# PCB_CoLAB_Schematic.net
KiCad netlist of a schematic drawn in EAGLE
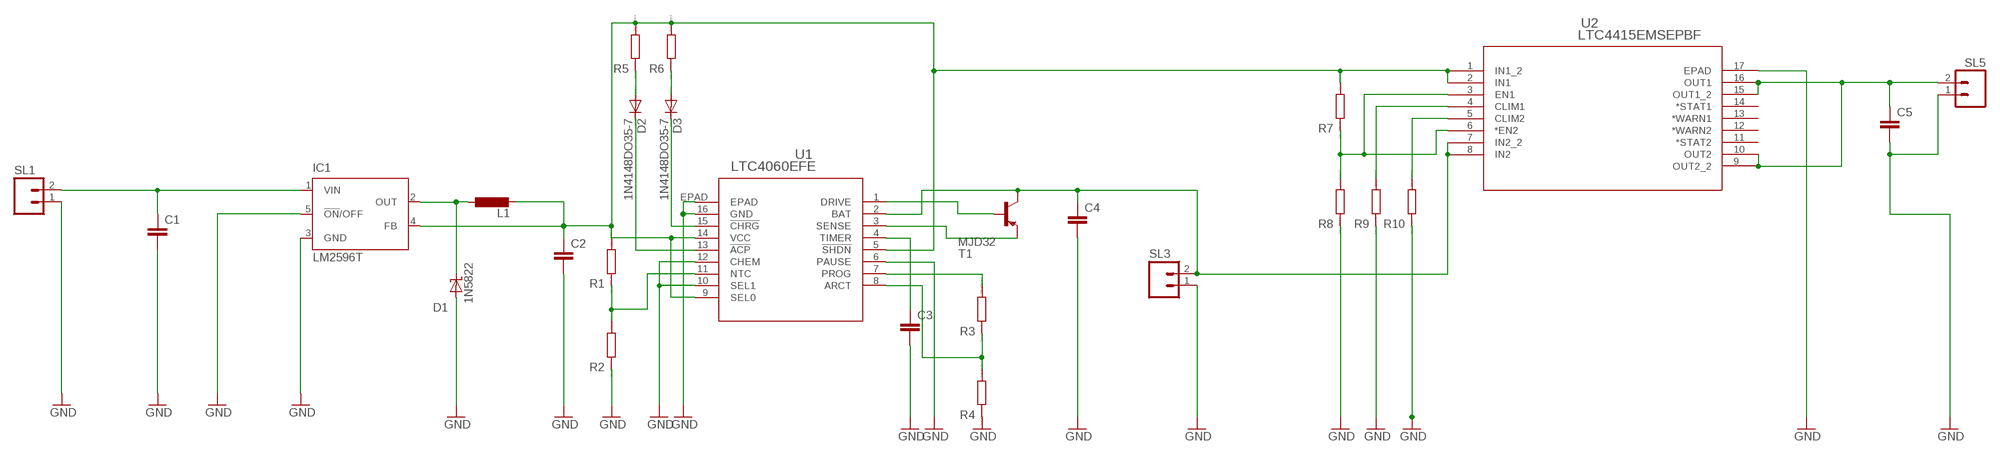
[diagram p0: schematic, sheet 1]

(export (version "E")
  (design (tool "Eeschema 10.0.6"))
  (components
    (comp (ref "C1")
      (value "C-EU025-024X044")
      (footprint "eagle-import:C025-024X044")
      (libsource (lib "eagle-import") (part "C-EU025-024X044"))
    )
    (comp (ref "C2")
      (value "C-EU025-024X044")
      (footprint "eagle-import:C025-024X044")
      (libsource (lib "eagle-import") (part "C-EU025-024X044"))
    )
    (comp (ref "C3")
      (value "C-EU025-024X044")
      (footprint "eagle-import:C025-024X044")
      (libsource (lib "eagle-import") (part "C-EU025-024X044"))
    )
    (comp (ref "C4")
      (value "C-EU025-024X044")
      (footprint "eagle-import:C025-024X044")
      (libsource (lib "eagle-import") (part "C-EU025-024X044"))
    )
    (comp (ref "C5")
      (value "C-EU025-024X044")
      (footprint "eagle-import:C025-024X044")
      (libsource (lib "eagle-import") (part "C-EU025-024X044"))
    )
    (comp (ref "D1")
      (value "1N5822")
      (footprint "eagle-import:DIOAD2120W130L950D530P")
      (fields (field (name "MF") "ON Semiconductor"))
      (libsource (lib "eagle-import") (part "1N5822"))
    )
    (comp (ref "D2")
      (value "1N4148DO35-7")
      (footprint "eagle-import:DO35-7")
      (libsource (lib "eagle-import") (part "1N4148DO35-7"))
    )
    (comp (ref "D3")
      (value "1N4148DO35-7")
      (footprint "eagle-import:DO35-7")
      (libsource (lib "eagle-import") (part "1N4148DO35-7"))
    )
    (comp (ref "IC1")
      (value "LM2596T")
      (footprint "eagle-import:T05D")
      (fields (field (name "MPN") "LM2596T-ADJ/LF02"))
      (libsource (lib "eagle-import") (part "LM2596T"))
    )
    (comp (ref "L1")
      (value "L-EU0204/7")
      (footprint "eagle-import:0204_7")
      (libsource (lib "eagle-import") (part "L-EU0204/7"))
    )
    (comp (ref "R1")
      (value "R0204/7")
      (footprint "eagle-import:0204_7")
      (libsource (lib "eagle-import") (part "R0204/7"))
    )
    (comp (ref "R2")
      (value "R0204/7")
      (footprint "eagle-import:0204_7")
      (libsource (lib "eagle-import") (part "R0204/7"))
    )
    (comp (ref "R3")
      (value "R0204/7")
      (footprint "eagle-import:0204_7")
      (libsource (lib "eagle-import") (part "R0204/7"))
    )
    (comp (ref "R4")
      (value "R0204/7")
      (footprint "eagle-import:0204_7")
      (libsource (lib "eagle-import") (part "R0204/7"))
    )
    (comp (ref "R5")
      (value "R0204/7")
      (footprint "eagle-import:0204_7")
      (libsource (lib "eagle-import") (part "R0204/7"))
    )
    (comp (ref "R6")
      (value "R0204/7")
      (footprint "eagle-import:0204_7")
      (libsource (lib "eagle-import") (part "R0204/7"))
    )
    (comp (ref "R7")
      (value "R0204/7")
      (footprint "eagle-import:0204_7")
      (libsource (lib "eagle-import") (part "R0204/7"))
    )
    (comp (ref "R8")
      (value "R0204/7")
      (footprint "eagle-import:0204_7")
      (libsource (lib "eagle-import") (part "R0204/7"))
    )
    (comp (ref "R9")
      (value "R0204/7")
      (footprint "eagle-import:0204_7")
      (libsource (lib "eagle-import") (part "R0204/7"))
    )
    (comp (ref "R10")
      (value "R0204/7")
      (footprint "eagle-import:0204_7")
      (libsource (lib "eagle-import") (part "R0204/7"))
    )
    (comp (ref "SL1")
      (value "M02")
      (footprint "eagle-import:02P")
      (libsource (lib "eagle-import") (part "M02"))
    )
    (comp (ref "SL3")
      (value "M02")
      (footprint "eagle-import:02P")
      (libsource (lib "eagle-import") (part "M02"))
    )
    (comp (ref "SL5")
      (value "M02")
      (footprint "eagle-import:02P")
      (libsource (lib "eagle-import") (part "M02"))
    )
    (comp (ref "T1")
      (value "MJD32")
      (footprint "eagle-import:DPAK")
      (libsource (lib "eagle-import") (part "MJD32"))
    )
    (comp (ref "U1")
      (value "LTC4060EFE")
      (footprint "eagle-import:TSSOP-16_FE_BC_LIT")
      (libsource (lib "eagle-import") (part "LTC4060EFE"))
    )
    (comp (ref "U2")
      (value "LTC4415EMSEPBF")
      (footprint "eagle-import:MSOP-16_MSE")
      (fields (field (name "MF") "Analog Devices") (field (name "MP") "LTC4415EMSE#PBF"))
      (libsource (lib "eagle-import") (part "LTC4415EMSEPBF"))
    )
  )
  (nets
    (net (code "1") (name "GND") (class "Default")
      (node (ref "C1") (pin "2") (pinfunction "2_2") (pintype "passive"))
      (node (ref "C2") (pin "2") (pinfunction "2_2") (pintype "passive"))
      (node (ref "C3") (pin "2") (pinfunction "2_2") (pintype "passive"))
      (node (ref "C4") (pin "2") (pinfunction "2_2") (pintype "passive"))
      (node (ref "C5") (pin "2") (pinfunction "2_2") (pintype "passive"))
      (node (ref "D1") (pin "A") (pinfunction "A_A") (pintype "passive"))
      (node (ref "IC1") (pin "3") (pinfunction "GND_3") (pintype "power_in"))
      (node (ref "IC1") (pin "5") (pinfunction "~{ON}/OFF_5") (pintype "input"))
      (node (ref "R10") (pin "1") (pinfunction "1_1") (pintype "passive"))
      (node (ref "R2") (pin "1") (pinfunction "1_1") (pintype "passive"))
      (node (ref "R4") (pin "1") (pinfunction "1_1") (pintype "passive"))
      (node (ref "R8") (pin "1") (pinfunction "1_1") (pintype "passive"))
      (node (ref "R9") (pin "1") (pinfunction "1_1") (pintype "passive"))
      (node (ref "SL1") (pin "1") (pinfunction "1_1") (pintype "passive"))
      (node (ref "SL3") (pin "1") (pinfunction "1_1") (pintype "passive"))
      (node (ref "SL5") (pin "1") (pinfunction "1_1") (pintype "passive"))
      (node (ref "U1") (pin "10") (pinfunction "SEL1_10") (pintype "input"))
      (node (ref "U1") (pin "12") (pinfunction "CHEM_12") (pintype "input"))
      (node (ref "U1") (pin "16") (pinfunction "GND_16") (pintype "power_in"))
      (node (ref "U1") (pin "6") (pinfunction "PAUSE_6") (pintype "input"))
      (node (ref "U1") (pin "EPAD") (pinfunction "EPAD_EPAD") (pintype "passive"))
      (node (ref "U2") (pin "17") (pinfunction "EPAD_17") (pintype "passive"))
    )
    (net (code "2") (name "Net-(D2-PadA)") (class "Default")
      (node (ref "D2") (pin "A") (pinfunction "A_A") (pintype "passive"))
      (node (ref "R5") (pin "1") (pinfunction "1_1") (pintype "passive"))
    )
    (net (code "3") (name "Net-(D3-PadA)") (class "Default")
      (node (ref "D3") (pin "A") (pinfunction "A_A") (pintype "passive"))
      (node (ref "R6") (pin "1") (pinfunction "1_1") (pintype "passive"))
    )
    (net (code "4") (name "Net-(IC1-FB)") (class "Default")
      (node (ref "C2") (pin "1") (pinfunction "1_1") (pintype "passive"))
      (node (ref "IC1") (pin "4") (pinfunction "FB_4") (pintype "input"))
      (node (ref "L1") (pin "2") (pinfunction "2_2") (pintype "passive"))
      (node (ref "R1") (pin "2") (pinfunction "2_2") (pintype "passive"))
      (node (ref "R5") (pin "2") (pinfunction "2_2") (pintype "passive"))
      (node (ref "R6") (pin "2") (pinfunction "2_2") (pintype "passive"))
      (node (ref "R7") (pin "2") (pinfunction "2_2") (pintype "passive"))
      (node (ref "U1") (pin "14") (pinfunction "VCC_14") (pintype "power_in"))
      (node (ref "U1") (pin "5") (pinfunction "~{SHDN}_5") (pintype "input"))
      (node (ref "U1") (pin "9") (pinfunction "SEL0_9") (pintype "input"))
      (node (ref "U2") (pin "1") (pinfunction "IN1_2_1") (pintype "input"))
      (node (ref "U2") (pin "2") (pinfunction "IN1_2") (pintype "input"))
    )
    (net (code "5") (name "Net-(IC1-OUT)") (class "Default")
      (node (ref "D1") (pin "C") (pinfunction "C_C") (pintype "passive"))
      (node (ref "IC1") (pin "2") (pinfunction "OUT_2") (pintype "output"))
      (node (ref "L1") (pin "1") (pinfunction "1_1") (pintype "passive"))
    )
    (net (code "6") (name "Net-(IC1-VIN)") (class "Default")
      (node (ref "C1") (pin "1") (pinfunction "1_1") (pintype "passive"))
      (node (ref "IC1") (pin "1") (pinfunction "VIN_1") (pintype "input"))
      (node (ref "SL1") (pin "2") (pinfunction "2_2") (pintype "passive"))
    )
    (net (code "7") (name "Net-(T1-B)") (class "Default")
      (node (ref "T1") (pin "1") (pinfunction "B_1") (pintype "passive"))
      (node (ref "U1") (pin "1") (pinfunction "DRIVE_1") (pintype "output"))
    )
    (net (code "8") (name "Net-(T1-C)") (class "Default")
      (node (ref "C4") (pin "1") (pinfunction "1_1") (pintype "passive"))
      (node (ref "SL3") (pin "2") (pinfunction "2_2") (pintype "passive"))
      (node (ref "T1") (pin "4") (pinfunction "C_4") (pintype "passive"))
      (node (ref "U1") (pin "2") (pinfunction "BAT_2") (pintype "input"))
      (node (ref "U2") (pin "7") (pinfunction "IN2_2_7") (pintype "input"))
      (node (ref "U2") (pin "8") (pinfunction "IN2_8") (pintype "input"))
    )
    (net (code "9") (name "Net-(T1-E)") (class "Default")
      (node (ref "T1") (pin "3") (pinfunction "E_3") (pintype "passive"))
      (node (ref "U1") (pin "3") (pinfunction "SENSE_3") (pintype "input"))
    )
    (net (code "10") (name "Net-(U1-ARCT)") (class "Default")
      (node (ref "R3") (pin "1") (pinfunction "1_1") (pintype "passive"))
      (node (ref "R4") (pin "2") (pinfunction "2_2") (pintype "passive"))
      (node (ref "U1") (pin "8") (pinfunction "ARCT_8") (pintype "input"))
    )
    (net (code "11") (name "Net-(U1-NTC)") (class "Default")
      (node (ref "R1") (pin "1") (pinfunction "1_1") (pintype "passive"))
      (node (ref "R2") (pin "2") (pinfunction "2_2") (pintype "passive"))
      (node (ref "U1") (pin "11") (pinfunction "NTC_11") (pintype "input"))
    )
    (net (code "12") (name "Net-(U1-PROG)") (class "Default")
      (node (ref "R3") (pin "2") (pinfunction "2_2") (pintype "passive"))
      (node (ref "U1") (pin "7") (pinfunction "PROG_7") (pintype "input"))
    )
    (net (code "13") (name "Net-(U1-TIMER)") (class "Default")
      (node (ref "C3") (pin "1") (pinfunction "1_1") (pintype "passive"))
      (node (ref "U1") (pin "4") (pinfunction "TIMER_4") (pintype "input"))
    )
    (net (code "14") (name "Net-(U1-~{ACP})") (class "Default")
      (node (ref "D2") (pin "C") (pinfunction "C_C") (pintype "passive"))
      (node (ref "U1") (pin "13") (pinfunction "~{ACP}_13") (pintype "output"))
    )
    (net (code "15") (name "Net-(U1-~{CHRG})") (class "Default")
      (node (ref "D3") (pin "C") (pinfunction "C_C") (pintype "passive"))
      (node (ref "U1") (pin "15") (pinfunction "~{CHRG}_15") (pintype "output"))
    )
    (net (code "16") (name "Net-(U2-*EN2)") (class "Default")
      (node (ref "R7") (pin "1") (pinfunction "1_1") (pintype "passive"))
      (node (ref "R8") (pin "2") (pinfunction "2_2") (pintype "passive"))
      (node (ref "U2") (pin "3") (pinfunction "EN1_3") (pintype "input"))
      (node (ref "U2") (pin "6") (pinfunction "*EN2_6") (pintype "input"))
    )
    (net (code "17") (name "Net-(U2-CLIM1)") (class "Default")
      (node (ref "R9") (pin "2") (pinfunction "2_2") (pintype "passive"))
      (node (ref "U2") (pin "4") (pinfunction "CLIM1_4") (pintype "passive"))
    )
    (net (code "18") (name "Net-(U2-CLIM2)") (class "Default")
      (node (ref "R10") (pin "2") (pinfunction "2_2") (pintype "passive"))
      (node (ref "U2") (pin "5") (pinfunction "CLIM2_5") (pintype "passive"))
    )
    (net (code "19") (name "Net-(U2-OUT1)") (class "Default")
      (node (ref "C5") (pin "1") (pinfunction "1_1") (pintype "passive"))
      (node (ref "SL5") (pin "2") (pinfunction "2_2") (pintype "passive"))
      (node (ref "U2") (pin "10") (pinfunction "OUT2_10") (pintype "output"))
      (node (ref "U2") (pin "15") (pinfunction "OUT1_2_15") (pintype "output"))
      (node (ref "U2") (pin "16") (pinfunction "OUT1_16") (pintype "output"))
      (node (ref "U2") (pin "9") (pinfunction "OUT2_2_9") (pintype "output"))
    )
    (net (code "20") (name "unconnected-(U2-*STAT1-Pad14)") (class "Default")
      (node (ref "U2") (pin "14") (pinfunction "*STAT1_14") (pintype "output"))
    )
    (net (code "21") (name "unconnected-(U2-*STAT2-Pad11)") (class "Default")
      (node (ref "U2") (pin "11") (pinfunction "*STAT2_11") (pintype "output"))
    )
    (net (code "22") (name "unconnected-(U2-*WARN1-Pad13)") (class "Default")
      (node (ref "U2") (pin "13") (pinfunction "*WARN1_13") (pintype "output"))
    )
    (net (code "23") (name "unconnected-(U2-*WARN2-Pad12)") (class "Default")
      (node (ref "U2") (pin "12") (pinfunction "*WARN2_12") (pintype "output"))
    )
  )
)
